# Sheet1.net
KiCad netlist of a schematic drawn in Altium Designer
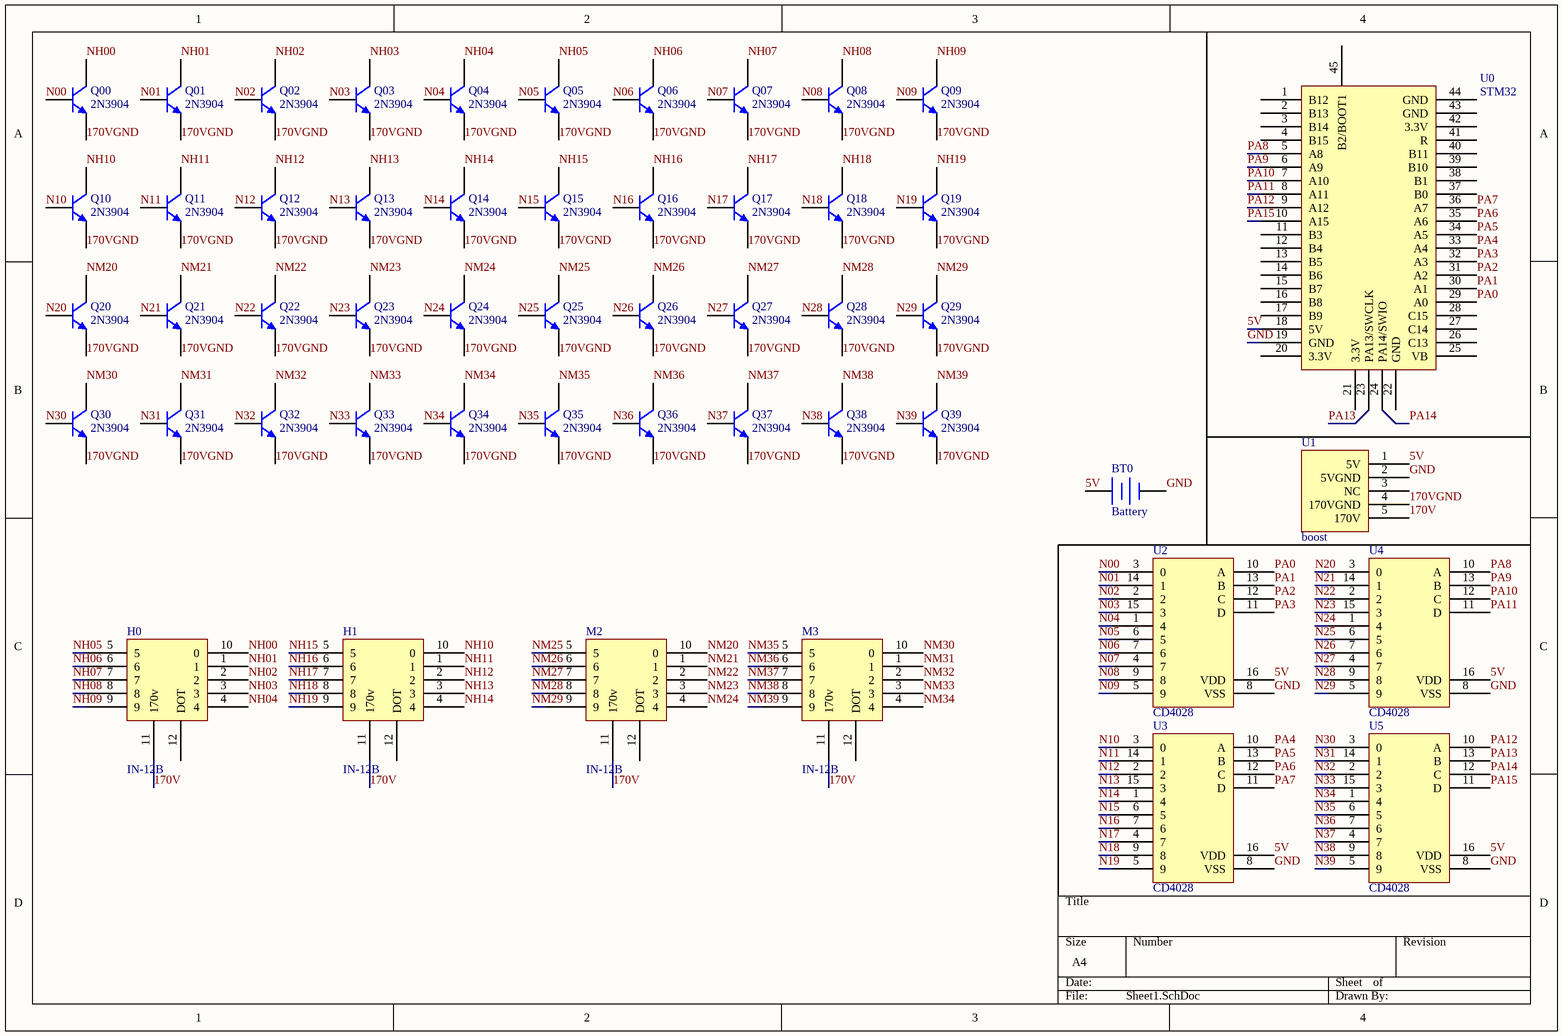
[diagram p0: Sheet1.SchDoc]

(export (version "E")
  (design (tool "Eeschema 10.0.6"))
  (components
    (comp (ref "BT0")
      (value "Battery")
      (footprint "BAT-2")
      (description "Multicell Battery")
      (fields (field (name "PUBLISHER") "Altium Limited"))
      (libsource (lib "Miscellaneous Devices") (part "Battery"))
    )
    (comp (ref "H0") (value "IN-12B") (footprint "IN-12B base") (libsource (lib "IN-12B") (part "IN-12B")))
    (comp (ref "H1") (value "IN-12B") (footprint "IN-12B base") (libsource (lib "IN-12B") (part "IN-12B")))
    (comp (ref "M2") (value "IN-12B") (footprint "IN-12B base") (libsource (lib "IN-12B") (part "IN-12B")))
    (comp (ref "M3") (value "IN-12B") (footprint "IN-12B base") (libsource (lib "IN-12B") (part "IN-12B")))
    (comp (ref "Q00")
      (value "2N3904")
      (footprint "PcbLib1:TO-92")
      (description "NPN General Purpose Amplifier")
      (fields (field (name "PUBLISHER") "Altium Limited"))
      (libsource (lib "Miscellaneous Devices") (part "2N3904"))
    )
    (comp (ref "Q01")
      (value "2N3904")
      (footprint "TO-92")
      (description "NPN General Purpose Amplifier")
      (fields (field (name "PUBLISHER") "Altium Limited"))
      (libsource (lib "Miscellaneous Devices") (part "2N3904"))
    )
    (comp (ref "Q02")
      (value "2N3904")
      (footprint "TO-92")
      (description "NPN General Purpose Amplifier")
      (fields (field (name "PUBLISHER") "Altium Limited"))
      (libsource (lib "Miscellaneous Devices") (part "2N3904"))
    )
    (comp (ref "Q03")
      (value "2N3904")
      (footprint "TO-92")
      (description "NPN General Purpose Amplifier")
      (fields (field (name "PUBLISHER") "Altium Limited"))
      (libsource (lib "Miscellaneous Devices") (part "2N3904"))
    )
    (comp (ref "Q04")
      (value "2N3904")
      (footprint "TO-92")
      (description "NPN General Purpose Amplifier")
      (fields (field (name "PUBLISHER") "Altium Limited"))
      (libsource (lib "Miscellaneous Devices") (part "2N3904"))
    )
    (comp (ref "Q05")
      (value "2N3904")
      (footprint "TO-92")
      (description "NPN General Purpose Amplifier")
      (fields (field (name "PUBLISHER") "Altium Limited"))
      (libsource (lib "Miscellaneous Devices") (part "2N3904"))
    )
    (comp (ref "Q06")
      (value "2N3904")
      (footprint "TO-92")
      (description "NPN General Purpose Amplifier")
      (fields (field (name "PUBLISHER") "Altium Limited"))
      (libsource (lib "Miscellaneous Devices") (part "2N3904"))
    )
    (comp (ref "Q07")
      (value "2N3904")
      (footprint "TO-92")
      (description "NPN General Purpose Amplifier")
      (fields (field (name "PUBLISHER") "Altium Limited"))
      (libsource (lib "Miscellaneous Devices") (part "2N3904"))
    )
    (comp (ref "Q08")
      (value "2N3904")
      (footprint "TO-92")
      (description "NPN General Purpose Amplifier")
      (fields (field (name "PUBLISHER") "Altium Limited"))
      (libsource (lib "Miscellaneous Devices") (part "2N3904"))
    )
    (comp (ref "Q09")
      (value "2N3904")
      (footprint "TO-92")
      (description "NPN General Purpose Amplifier")
      (fields (field (name "PUBLISHER") "Altium Limited"))
      (libsource (lib "Miscellaneous Devices") (part "2N3904"))
    )
    (comp (ref "Q10")
      (value "2N3904")
      (footprint "TO-92")
      (description "NPN General Purpose Amplifier")
      (fields (field (name "PUBLISHER") "Altium Limited"))
      (libsource (lib "Miscellaneous Devices") (part "2N3904"))
    )
    (comp (ref "Q11")
      (value "2N3904")
      (footprint "TO-92")
      (description "NPN General Purpose Amplifier")
      (fields (field (name "PUBLISHER") "Altium Limited"))
      (libsource (lib "Miscellaneous Devices") (part "2N3904"))
    )
    (comp (ref "Q12")
      (value "2N3904")
      (footprint "TO-92")
      (description "NPN General Purpose Amplifier")
      (fields (field (name "PUBLISHER") "Altium Limited"))
      (libsource (lib "Miscellaneous Devices") (part "2N3904"))
    )
    (comp (ref "Q13")
      (value "2N3904")
      (footprint "TO-92")
      (description "NPN General Purpose Amplifier")
      (fields (field (name "PUBLISHER") "Altium Limited"))
      (libsource (lib "Miscellaneous Devices") (part "2N3904"))
    )
    (comp (ref "Q14")
      (value "2N3904")
      (footprint "TO-92")
      (description "NPN General Purpose Amplifier")
      (fields (field (name "PUBLISHER") "Altium Limited"))
      (libsource (lib "Miscellaneous Devices") (part "2N3904"))
    )
    (comp (ref "Q15")
      (value "2N3904")
      (footprint "TO-92")
      (description "NPN General Purpose Amplifier")
      (fields (field (name "PUBLISHER") "Altium Limited"))
      (libsource (lib "Miscellaneous Devices") (part "2N3904"))
    )
    (comp (ref "Q16")
      (value "2N3904")
      (footprint "TO-92")
      (description "NPN General Purpose Amplifier")
      (fields (field (name "PUBLISHER") "Altium Limited"))
      (libsource (lib "Miscellaneous Devices") (part "2N3904"))
    )
    (comp (ref "Q17")
      (value "2N3904")
      (footprint "TO-92")
      (description "NPN General Purpose Amplifier")
      (fields (field (name "PUBLISHER") "Altium Limited"))
      (libsource (lib "Miscellaneous Devices") (part "2N3904"))
    )
    (comp (ref "Q18")
      (value "2N3904")
      (footprint "TO-92")
      (description "NPN General Purpose Amplifier")
      (fields (field (name "PUBLISHER") "Altium Limited"))
      (libsource (lib "Miscellaneous Devices") (part "2N3904"))
    )
    (comp (ref "Q19")
      (value "2N3904")
      (footprint "TO-92")
      (description "NPN General Purpose Amplifier")
      (fields (field (name "PUBLISHER") "Altium Limited"))
      (libsource (lib "Miscellaneous Devices") (part "2N3904"))
    )
    (comp (ref "Q20")
      (value "2N3904")
      (footprint "TO-92")
      (description "NPN General Purpose Amplifier")
      (fields (field (name "PUBLISHER") "Altium Limited"))
      (libsource (lib "Miscellaneous Devices") (part "2N3904"))
    )
    (comp (ref "Q21")
      (value "2N3904")
      (footprint "TO-92")
      (description "NPN General Purpose Amplifier")
      (fields (field (name "PUBLISHER") "Altium Limited"))
      (libsource (lib "Miscellaneous Devices") (part "2N3904"))
    )
    (comp (ref "Q22")
      (value "2N3904")
      (footprint "TO-92")
      (description "NPN General Purpose Amplifier")
      (fields (field (name "PUBLISHER") "Altium Limited"))
      (libsource (lib "Miscellaneous Devices") (part "2N3904"))
    )
    (comp (ref "Q23")
      (value "2N3904")
      (footprint "TO-92")
      (description "NPN General Purpose Amplifier")
      (fields (field (name "PUBLISHER") "Altium Limited"))
      (libsource (lib "Miscellaneous Devices") (part "2N3904"))
    )
    (comp (ref "Q24")
      (value "2N3904")
      (footprint "TO-92")
      (description "NPN General Purpose Amplifier")
      (fields (field (name "PUBLISHER") "Altium Limited"))
      (libsource (lib "Miscellaneous Devices") (part "2N3904"))
    )
    (comp (ref "Q25")
      (value "2N3904")
      (footprint "TO-92")
      (description "NPN General Purpose Amplifier")
      (fields (field (name "PUBLISHER") "Altium Limited"))
      (libsource (lib "Miscellaneous Devices") (part "2N3904"))
    )
    (comp (ref "Q26")
      (value "2N3904")
      (footprint "TO-92")
      (description "NPN General Purpose Amplifier")
      (fields (field (name "PUBLISHER") "Altium Limited"))
      (libsource (lib "Miscellaneous Devices") (part "2N3904"))
    )
    (comp (ref "Q27")
      (value "2N3904")
      (footprint "TO-92")
      (description "NPN General Purpose Amplifier")
      (fields (field (name "PUBLISHER") "Altium Limited"))
      (libsource (lib "Miscellaneous Devices") (part "2N3904"))
    )
    (comp (ref "Q28")
      (value "2N3904")
      (footprint "TO-92")
      (description "NPN General Purpose Amplifier")
      (fields (field (name "PUBLISHER") "Altium Limited"))
      (libsource (lib "Miscellaneous Devices") (part "2N3904"))
    )
    (comp (ref "Q29")
      (value "2N3904")
      (footprint "TO-92")
      (description "NPN General Purpose Amplifier")
      (fields (field (name "PUBLISHER") "Altium Limited"))
      (libsource (lib "Miscellaneous Devices") (part "2N3904"))
    )
    (comp (ref "Q30")
      (value "2N3904")
      (footprint "TO-92")
      (description "NPN General Purpose Amplifier")
      (fields (field (name "PUBLISHER") "Altium Limited"))
      (libsource (lib "Miscellaneous Devices") (part "2N3904"))
    )
    (comp (ref "Q31")
      (value "2N3904")
      (footprint "TO-92")
      (description "NPN General Purpose Amplifier")
      (fields (field (name "PUBLISHER") "Altium Limited"))
      (libsource (lib "Miscellaneous Devices") (part "2N3904"))
    )
    (comp (ref "Q32")
      (value "2N3904")
      (footprint "TO-92")
      (description "NPN General Purpose Amplifier")
      (fields (field (name "PUBLISHER") "Altium Limited"))
      (libsource (lib "Miscellaneous Devices") (part "2N3904"))
    )
    (comp (ref "Q33")
      (value "2N3904")
      (footprint "TO-92")
      (description "NPN General Purpose Amplifier")
      (fields (field (name "PUBLISHER") "Altium Limited"))
      (libsource (lib "Miscellaneous Devices") (part "2N3904"))
    )
    (comp (ref "Q34")
      (value "2N3904")
      (footprint "TO-92")
      (description "NPN General Purpose Amplifier")
      (fields (field (name "PUBLISHER") "Altium Limited"))
      (libsource (lib "Miscellaneous Devices") (part "2N3904"))
    )
    (comp (ref "Q35")
      (value "2N3904")
      (footprint "TO-92")
      (description "NPN General Purpose Amplifier")
      (fields (field (name "PUBLISHER") "Altium Limited"))
      (libsource (lib "Miscellaneous Devices") (part "2N3904"))
    )
    (comp (ref "Q36")
      (value "2N3904")
      (footprint "TO-92")
      (description "NPN General Purpose Amplifier")
      (fields (field (name "PUBLISHER") "Altium Limited"))
      (libsource (lib "Miscellaneous Devices") (part "2N3904"))
    )
    (comp (ref "Q37")
      (value "2N3904")
      (footprint "TO-92")
      (description "NPN General Purpose Amplifier")
      (fields (field (name "PUBLISHER") "Altium Limited"))
      (libsource (lib "Miscellaneous Devices") (part "2N3904"))
    )
    (comp (ref "Q38")
      (value "2N3904")
      (footprint "TO-92")
      (description "NPN General Purpose Amplifier")
      (fields (field (name "PUBLISHER") "Altium Limited"))
      (libsource (lib "Miscellaneous Devices") (part "2N3904"))
    )
    (comp (ref "Q39")
      (value "2N3904")
      (footprint "TO-92")
      (description "NPN General Purpose Amplifier")
      (fields (field (name "PUBLISHER") "Altium Limited"))
      (libsource (lib "Miscellaneous Devices") (part "2N3904"))
    )
    (comp (ref "U0") (value "STM32") (footprint "STM32") (libsource (lib "stm32") (part "STM32")))
    (comp (ref "U1") (value "boost") (footprint "HDR1X5") (libsource (lib "boost") (part "boost")))
    (comp (ref "U2") (value "CD4028") (footprint "CD4028") (libsource (lib "CD4028") (part "CD4028")))
    (comp (ref "U3") (value "CD4028") (footprint "CD4028") (libsource (lib "CD4028") (part "CD4028")))
    (comp (ref "U4") (value "CD4028") (footprint "CD4028") (libsource (lib "CD4028") (part "CD4028")))
    (comp (ref "U5") (value "CD4028") (footprint "CD4028") (libsource (lib "CD4028") (part "CD4028")))
  )
  (nets
    (net (code "1") (name "/5V") (class "Default")
      (node (ref "BT0") (pin "1") (pinfunction "+_1") (pintype "passive"))
      (node (ref "U0") (pin "18") (pinfunction "5V_18") (pintype "passive"))
      (node (ref "U1") (pin "1") (pinfunction "5V_1") (pintype "passive"))
      (node (ref "U2") (pin "16") (pinfunction "VDD_16") (pintype "passive"))
      (node (ref "U3") (pin "16") (pinfunction "VDD_16") (pintype "passive"))
      (node (ref "U4") (pin "16") (pinfunction "VDD_16") (pintype "passive"))
      (node (ref "U5") (pin "16") (pinfunction "VDD_16") (pintype "passive"))
    )
    (net (code "2") (name "/170V") (class "Default")
      (node (ref "H0") (pin "11") (pinfunction "170v_11") (pintype "passive"))
      (node (ref "H1") (pin "11") (pinfunction "170v_11") (pintype "passive"))
      (node (ref "M2") (pin "11") (pinfunction "170v_11") (pintype "passive"))
      (node (ref "M3") (pin "11") (pinfunction "170v_11") (pintype "passive"))
      (node (ref "U1") (pin "5") (pinfunction "170V_5") (pintype "passive"))
    )
    (net (code "3") (name "/170VGND") (class "Default")
      (node (ref "Q00") (pin "1") (pinfunction "E_1") (pintype "passive"))
      (node (ref "Q01") (pin "1") (pinfunction "E_1") (pintype "passive"))
      (node (ref "Q02") (pin "1") (pinfunction "E_1") (pintype "passive"))
      (node (ref "Q03") (pin "1") (pinfunction "E_1") (pintype "passive"))
      (node (ref "Q04") (pin "1") (pinfunction "E_1") (pintype "passive"))
      (node (ref "Q05") (pin "1") (pinfunction "E_1") (pintype "passive"))
      (node (ref "Q06") (pin "1") (pinfunction "E_1") (pintype "passive"))
      (node (ref "Q07") (pin "1") (pinfunction "E_1") (pintype "passive"))
      (node (ref "Q08") (pin "1") (pinfunction "E_1") (pintype "passive"))
      (node (ref "Q09") (pin "1") (pinfunction "E_1") (pintype "passive"))
      (node (ref "Q10") (pin "1") (pinfunction "E_1") (pintype "passive"))
      (node (ref "Q11") (pin "1") (pinfunction "E_1") (pintype "passive"))
      (node (ref "Q12") (pin "1") (pinfunction "E_1") (pintype "passive"))
      (node (ref "Q13") (pin "1") (pinfunction "E_1") (pintype "passive"))
      (node (ref "Q14") (pin "1") (pinfunction "E_1") (pintype "passive"))
      (node (ref "Q15") (pin "1") (pinfunction "E_1") (pintype "passive"))
      (node (ref "Q16") (pin "1") (pinfunction "E_1") (pintype "passive"))
      (node (ref "Q17") (pin "1") (pinfunction "E_1") (pintype "passive"))
      (node (ref "Q18") (pin "1") (pinfunction "E_1") (pintype "passive"))
      (node (ref "Q19") (pin "1") (pinfunction "E_1") (pintype "passive"))
      (node (ref "Q20") (pin "1") (pinfunction "E_1") (pintype "passive"))
      (node (ref "Q21") (pin "1") (pinfunction "E_1") (pintype "passive"))
      (node (ref "Q22") (pin "1") (pinfunction "E_1") (pintype "passive"))
      (node (ref "Q23") (pin "1") (pinfunction "E_1") (pintype "passive"))
      (node (ref "Q24") (pin "1") (pinfunction "E_1") (pintype "passive"))
      (node (ref "Q25") (pin "1") (pinfunction "E_1") (pintype "passive"))
      (node (ref "Q26") (pin "1") (pinfunction "E_1") (pintype "passive"))
      (node (ref "Q27") (pin "1") (pinfunction "E_1") (pintype "passive"))
      (node (ref "Q28") (pin "1") (pinfunction "E_1") (pintype "passive"))
      (node (ref "Q29") (pin "1") (pinfunction "E_1") (pintype "passive"))
      (node (ref "Q30") (pin "1") (pinfunction "E_1") (pintype "passive"))
      (node (ref "Q31") (pin "1") (pinfunction "E_1") (pintype "passive"))
      (node (ref "Q32") (pin "1") (pinfunction "E_1") (pintype "passive"))
      (node (ref "Q33") (pin "1") (pinfunction "E_1") (pintype "passive"))
      (node (ref "Q34") (pin "1") (pinfunction "E_1") (pintype "passive"))
      (node (ref "Q35") (pin "1") (pinfunction "E_1") (pintype "passive"))
      (node (ref "Q36") (pin "1") (pinfunction "E_1") (pintype "passive"))
      (node (ref "Q37") (pin "1") (pinfunction "E_1") (pintype "passive"))
      (node (ref "Q38") (pin "1") (pinfunction "E_1") (pintype "passive"))
      (node (ref "Q39") (pin "1") (pinfunction "E_1") (pintype "passive"))
      (node (ref "U1") (pin "4") (pinfunction "170VGND_4") (pintype "passive"))
    )
    (net (code "4") (name "/GND") (class "Default")
      (node (ref "BT0") (pin "2") (pinfunction "-_2") (pintype "passive"))
      (node (ref "U0") (pin "19") (pinfunction "GND_19") (pintype "passive"))
      (node (ref "U1") (pin "2") (pinfunction "5VGND_2") (pintype "passive"))
      (node (ref "U2") (pin "8") (pinfunction "VSS_8") (pintype "passive"))
      (node (ref "U3") (pin "8") (pinfunction "VSS_8") (pintype "passive"))
      (node (ref "U4") (pin "8") (pinfunction "VSS_8") (pintype "passive"))
      (node (ref "U5") (pin "8") (pinfunction "VSS_8") (pintype "passive"))
    )
    (net (code "5") (name "/N00") (class "Default")
      (node (ref "Q00") (pin "2") (pinfunction "B_2") (pintype "passive"))
      (node (ref "U2") (pin "3") (pinfunction "0_3") (pintype "passive"))
    )
    (net (code "6") (name "/N01") (class "Default")
      (node (ref "Q01") (pin "2") (pinfunction "B_2") (pintype "passive"))
      (node (ref "U2") (pin "14") (pinfunction "1_14") (pintype "passive"))
    )
    (net (code "7") (name "/N02") (class "Default")
      (node (ref "Q02") (pin "2") (pinfunction "B_2") (pintype "passive"))
      (node (ref "U2") (pin "2") (pinfunction "2_2") (pintype "passive"))
    )
    (net (code "8") (name "/N03") (class "Default")
      (node (ref "Q03") (pin "2") (pinfunction "B_2") (pintype "passive"))
      (node (ref "U2") (pin "15") (pinfunction "3_15") (pintype "passive"))
    )
    (net (code "9") (name "/N04") (class "Default")
      (node (ref "Q04") (pin "2") (pinfunction "B_2") (pintype "passive"))
      (node (ref "U2") (pin "1") (pinfunction "4_1") (pintype "passive"))
    )
    (net (code "10") (name "/N05") (class "Default")
      (node (ref "Q05") (pin "2") (pinfunction "B_2") (pintype "passive"))
      (node (ref "U2") (pin "6") (pinfunction "5_6") (pintype "passive"))
    )
    (net (code "11") (name "/N06") (class "Default")
      (node (ref "Q06") (pin "2") (pinfunction "B_2") (pintype "passive"))
      (node (ref "U2") (pin "7") (pinfunction "6_7") (pintype "passive"))
    )
    (net (code "12") (name "/N07") (class "Default")
      (node (ref "Q07") (pin "2") (pinfunction "B_2") (pintype "passive"))
      (node (ref "U2") (pin "4") (pinfunction "7_4") (pintype "passive"))
    )
    (net (code "13") (name "/N08") (class "Default")
      (node (ref "Q08") (pin "2") (pinfunction "B_2") (pintype "passive"))
      (node (ref "U2") (pin "9") (pinfunction "8_9") (pintype "passive"))
    )
    (net (code "14") (name "/N09") (class "Default")
      (node (ref "Q09") (pin "2") (pinfunction "B_2") (pintype "passive"))
      (node (ref "U2") (pin "5") (pinfunction "9_5") (pintype "passive"))
    )
    (net (code "15") (name "/N10") (class "Default")
      (node (ref "Q10") (pin "2") (pinfunction "B_2") (pintype "passive"))
      (node (ref "U3") (pin "3") (pinfunction "0_3") (pintype "passive"))
    )
    (net (code "16") (name "/N11") (class "Default")
      (node (ref "Q11") (pin "2") (pinfunction "B_2") (pintype "passive"))
      (node (ref "U3") (pin "14") (pinfunction "1_14") (pintype "passive"))
    )
    (net (code "17") (name "/N12") (class "Default")
      (node (ref "Q12") (pin "2") (pinfunction "B_2") (pintype "passive"))
      (node (ref "U3") (pin "2") (pinfunction "2_2") (pintype "passive"))
    )
    (net (code "18") (name "/N13") (class "Default")
      (node (ref "Q13") (pin "2") (pinfunction "B_2") (pintype "passive"))
      (node (ref "U3") (pin "15") (pinfunction "3_15") (pintype "passive"))
    )
    (net (code "19") (name "/N14") (class "Default")
      (node (ref "Q14") (pin "2") (pinfunction "B_2") (pintype "passive"))
      (node (ref "U3") (pin "1") (pinfunction "4_1") (pintype "passive"))
    )
    (net (code "20") (name "/N15") (class "Default")
      (node (ref "Q15") (pin "2") (pinfunction "B_2") (pintype "passive"))
      (node (ref "U3") (pin "6") (pinfunction "5_6") (pintype "passive"))
    )
    (net (code "21") (name "/N16") (class "Default")
      (node (ref "Q16") (pin "2") (pinfunction "B_2") (pintype "passive"))
      (node (ref "U3") (pin "7") (pinfunction "6_7") (pintype "passive"))
    )
    (net (code "22") (name "/N17") (class "Default")
      (node (ref "Q17") (pin "2") (pinfunction "B_2") (pintype "passive"))
      (node (ref "U3") (pin "4") (pinfunction "7_4") (pintype "passive"))
    )
    (net (code "23") (name "/N18") (class "Default")
      (node (ref "Q18") (pin "2") (pinfunction "B_2") (pintype "passive"))
      (node (ref "U3") (pin "9") (pinfunction "8_9") (pintype "passive"))
    )
    (net (code "24") (name "/N19") (class "Default")
      (node (ref "Q19") (pin "2") (pinfunction "B_2") (pintype "passive"))
      (node (ref "U3") (pin "5") (pinfunction "9_5") (pintype "passive"))
    )
    (net (code "25") (name "/N20") (class "Default")
      (node (ref "Q20") (pin "2") (pinfunction "B_2") (pintype "passive"))
      (node (ref "U4") (pin "3") (pinfunction "0_3") (pintype "passive"))
    )
    (net (code "26") (name "/N21") (class "Default")
      (node (ref "Q21") (pin "2") (pinfunction "B_2") (pintype "passive"))
      (node (ref "U4") (pin "14") (pinfunction "1_14") (pintype "passive"))
    )
    (net (code "27") (name "/N22") (class "Default")
      (node (ref "Q22") (pin "2") (pinfunction "B_2") (pintype "passive"))
      (node (ref "U4") (pin "2") (pinfunction "2_2") (pintype "passive"))
    )
    (net (code "28") (name "/N23") (class "Default")
      (node (ref "Q23") (pin "2") (pinfunction "B_2") (pintype "passive"))
      (node (ref "U4") (pin "15") (pinfunction "3_15") (pintype "passive"))
    )
    (net (code "29") (name "/N24") (class "Default")
      (node (ref "Q24") (pin "2") (pinfunction "B_2") (pintype "passive"))
      (node (ref "U4") (pin "1") (pinfunction "4_1") (pintype "passive"))
    )
    (net (code "30") (name "/N25") (class "Default")
      (node (ref "Q25") (pin "2") (pinfunction "B_2") (pintype "passive"))
      (node (ref "U4") (pin "6") (pinfunction "5_6") (pintype "passive"))
    )
    (net (code "31") (name "/N26") (class "Default")
      (node (ref "Q26") (pin "2") (pinfunction "B_2") (pintype "passive"))
      (node (ref "U4") (pin "7") (pinfunction "6_7") (pintype "passive"))
    )
    (net (code "32") (name "/N27") (class "Default")
      (node (ref "Q27") (pin "2") (pinfunction "B_2") (pintype "passive"))
      (node (ref "U4") (pin "4") (pinfunction "7_4") (pintype "passive"))
    )
    (net (code "33") (name "/N28") (class "Default")
      (node (ref "Q28") (pin "2") (pinfunction "B_2") (pintype "passive"))
      (node (ref "U4") (pin "9") (pinfunction "8_9") (pintype "passive"))
    )
    (net (code "34") (name "/N29") (class "Default")
      (node (ref "Q29") (pin "2") (pinfunction "B_2") (pintype "passive"))
      (node (ref "U4") (pin "5") (pinfunction "9_5") (pintype "passive"))
    )
    (net (code "35") (name "/N30") (class "Default")
      (node (ref "Q30") (pin "2") (pinfunction "B_2") (pintype "passive"))
      (node (ref "U5") (pin "3") (pinfunction "0_3") (pintype "passive"))
    )
    (net (code "36") (name "/N31") (class "Default")
      (node (ref "Q31") (pin "2") (pinfunction "B_2") (pintype "passive"))
      (node (ref "U5") (pin "14") (pinfunction "1_14") (pintype "passive"))
    )
    (net (code "37") (name "/N32") (class "Default")
      (node (ref "Q32") (pin "2") (pinfunction "B_2") (pintype "passive"))
      (node (ref "U5") (pin "2") (pinfunction "2_2") (pintype "passive"))
    )
    (net (code "38") (name "/N33") (class "Default")
      (node (ref "Q33") (pin "2") (pinfunction "B_2") (pintype "passive"))
      (node (ref "U5") (pin "15") (pinfunction "3_15") (pintype "passive"))
    )
    (net (code "39") (name "/N34") (class "Default")
      (node (ref "Q34") (pin "2") (pinfunction "B_2") (pintype "passive"))
      (node (ref "U5") (pin "1") (pinfunction "4_1") (pintype "passive"))
    )
    (net (code "40") (name "/N35") (class "Default")
      (node (ref "Q35") (pin "2") (pinfunction "B_2") (pintype "passive"))
      (node (ref "U5") (pin "6") (pinfunction "5_6") (pintype "passive"))
    )
    (net (code "41") (name "/N36") (class "Default")
      (node (ref "Q36") (pin "2") (pinfunction "B_2") (pintype "passive"))
      (node (ref "U5") (pin "7") (pinfunction "6_7") (pintype "passive"))
    )
    (net (code "42") (name "/N37") (class "Default")
      (node (ref "Q37") (pin "2") (pinfunction "B_2") (pintype "passive"))
      (node (ref "U5") (pin "4") (pinfunction "7_4") (pintype "passive"))
    )
    (net (code "43") (name "/N38") (class "Default")
      (node (ref "Q38") (pin "2") (pinfunction "B_2") (pintype "passive"))
      (node (ref "U5") (pin "9") (pinfunction "8_9") (pintype "passive"))
    )
    (net (code "44") (name "/N39") (class "Default")
      (node (ref "Q39") (pin "2") (pinfunction "B_2") (pintype "passive"))
      (node (ref "U5") (pin "5") (pinfunction "9_5") (pintype "passive"))
    )
    (net (code "45") (name "/NH00") (class "Default")
      (node (ref "H0") (pin "10") (pinfunction "0_10") (pintype "passive"))
      (node (ref "Q00") (pin "3") (pinfunction "C_3") (pintype "passive"))
    )
    (net (code "46") (name "/NH01") (class "Default")
      (node (ref "H0") (pin "1") (pinfunction "1_1") (pintype "passive"))
      (node (ref "Q01") (pin "3") (pinfunction "C_3") (pintype "passive"))
    )
    (net (code "47") (name "/NH02") (class "Default")
      (node (ref "H0") (pin "2") (pinfunction "2_2") (pintype "passive"))
      (node (ref "Q02") (pin "3") (pinfunction "C_3") (pintype "passive"))
    )
    (net (code "48") (name "/NH03") (class "Default")
      (node (ref "H0") (pin "3") (pinfunction "3_3") (pintype "passive"))
      (node (ref "Q03") (pin "3") (pinfunction "C_3") (pintype "passive"))
    )
    (net (code "49") (name "/NH04") (class "Default")
      (node (ref "H0") (pin "4") (pinfunction "4_4") (pintype "passive"))
      (node (ref "Q04") (pin "3") (pinfunction "C_3") (pintype "passive"))
    )
    (net (code "50") (name "/NH05") (class "Default")
      (node (ref "H0") (pin "5") (pinfunction "5_5") (pintype "passive"))
      (node (ref "Q05") (pin "3") (pinfunction "C_3") (pintype "passive"))
    )
    (net (code "51") (name "/NH06") (class "Default")
      (node (ref "H0") (pin "6") (pinfunction "6_6") (pintype "passive"))
      (node (ref "Q06") (pin "3") (pinfunction "C_3") (pintype "passive"))
    )
    (net (code "52") (name "/NH07") (class "Default")
      (node (ref "H0") (pin "7") (pinfunction "7_7") (pintype "passive"))
      (node (ref "Q07") (pin "3") (pinfunction "C_3") (pintype "passive"))
    )
    (net (code "53") (name "/NH08") (class "Default")
      (node (ref "H0") (pin "8") (pinfunction "8_8") (pintype "passive"))
      (node (ref "Q08") (pin "3") (pinfunction "C_3") (pintype "passive"))
    )
    (net (code "54") (name "/NH09") (class "Default")
      (node (ref "H0") (pin "9") (pinfunction "9_9") (pintype "passive"))
      (node (ref "Q09") (pin "3") (pinfunction "C_3") (pintype "passive"))
    )
    (net (code "55") (name "/NH10") (class "Default")
      (node (ref "H1") (pin "10") (pinfunction "0_10") (pintype "passive"))
      (node (ref "Q10") (pin "3") (pinfunction "C_3") (pintype "passive"))
    )
    (net (code "56") (name "/NH11") (class "Default")
      (node (ref "H1") (pin "1") (pinfunction "1_1") (pintype "passive"))
      (node (ref "Q11") (pin "3") (pinfunction "C_3") (pintype "passive"))
    )
    (net (code "57") (name "/NH12") (class "Default")
      (node (ref "H1") (pin "2") (pinfunction "2_2") (pintype "passive"))
      (node (ref "Q12") (pin "3") (pinfunction "C_3") (pintype "passive"))
    )
    (net (code "58") (name "/NH13") (class "Default")
      (node (ref "H1") (pin "3") (pinfunction "3_3") (pintype "passive"))
      (node (ref "Q13") (pin "3") (pinfunction "C_3") (pintype "passive"))
    )
    (net (code "59") (name "/NH14") (class "Default")
      (node (ref "H1") (pin "4") (pinfunction "4_4") (pintype "passive"))
      (node (ref "Q14") (pin "3") (pinfunction "C_3") (pintype "passive"))
    )
    (net (code "60") (name "/NH15") (class "Default")
      (node (ref "H1") (pin "5") (pinfunction "5_5") (pintype "passive"))
      (node (ref "Q15") (pin "3") (pinfunction "C_3") (pintype "passive"))
    )
    (net (code "61") (name "/NH16") (class "Default")
      (node (ref "H1") (pin "6") (pinfunction "6_6") (pintype "passive"))
      (node (ref "Q16") (pin "3") (pinfunction "C_3") (pintype "passive"))
    )
    (net (code "62") (name "/NH17") (class "Default")
      (node (ref "H1") (pin "7") (pinfunction "7_7") (pintype "passive"))
      (node (ref "Q17") (pin "3") (pinfunction "C_3") (pintype "passive"))
    )
    (net (code "63") (name "/NH18") (class "Default")
      (node (ref "H1") (pin "8") (pinfunction "8_8") (pintype "passive"))
      (node (ref "Q18") (pin "3") (pinfunction "C_3") (pintype "passive"))
    )
    (net (code "64") (name "/NH19") (class "Default")
      (node (ref "H1") (pin "9") (pinfunction "9_9") (pintype "passive"))
      (node (ref "Q19") (pin "3") (pinfunction "C_3") (pintype "passive"))
    )
    (net (code "65") (name "/NM20") (class "Default")
      (node (ref "M2") (pin "10") (pinfunction "0_10") (pintype "passive"))
      (node (ref "Q20") (pin "3") (pinfunction "C_3") (pintype "passive"))
    )
    (net (code "66") (name "/NM21") (class "Default")
      (node (ref "M2") (pin "1") (pinfunction "1_1") (pintype "passive"))
      (node (ref "Q21") (pin "3") (pinfunction "C_3") (pintype "passive"))
    )
    (net (code "67") (name "/NM22") (class "Default")
      (node (ref "M2") (pin "2") (pinfunction "2_2") (pintype "passive"))
      (node (ref "Q22") (pin "3") (pinfunction "C_3") (pintype "passive"))
    )
    (net (code "68") (name "/NM23") (class "Default")
      (node (ref "M2") (pin "3") (pinfunction "3_3") (pintype "passive"))
      (node (ref "Q23") (pin "3") (pinfunction "C_3") (pintype "passive"))
    )
    (net (code "69") (name "/NM24") (class "Default")
      (node (ref "M2") (pin "4") (pinfunction "4_4") (pintype "passive"))
      (node (ref "Q24") (pin "3") (pinfunction "C_3") (pintype "passive"))
    )
    (net (code "70") (name "/NM25") (class "Default")
      (node (ref "M2") (pin "5") (pinfunction "5_5") (pintype "passive"))
      (node (ref "Q25") (pin "3") (pinfunction "C_3") (pintype "passive"))
    )
    (net (code "71") (name "/NM26") (class "Default")
      (node (ref "M2") (pin "6") (pinfunction "6_6") (pintype "passive"))
      (node (ref "Q26") (pin "3") (pinfunction "C_3") (pintype "passive"))
    )
    (net (code "72") (name "/NM27") (class "Default")
      (node (ref "M2") (pin "7") (pinfunction "7_7") (pintype "passive"))
      (node (ref "Q27") (pin "3") (pinfunction "C_3") (pintype "passive"))
    )
    (net (code "73") (name "/NM28") (class "Default")
      (node (ref "M2") (pin "8") (pinfunction "8_8") (pintype "passive"))
      (node (ref "Q28") (pin "3") (pinfunction "C_3") (pintype "passive"))
    )
    (net (code "74") (name "/NM29") (class "Default")
      (node (ref "M2") (pin "9") (pinfunction "9_9") (pintype "passive"))
      (node (ref "Q29") (pin "3") (pinfunction "C_3") (pintype "passive"))
    )
    (net (code "75") (name "/NM30") (class "Default")
      (node (ref "M3") (pin "10") (pinfunction "0_10") (pintype "passive"))
      (node (ref "Q30") (pin "3") (pinfunction "C_3") (pintype "passive"))
    )
    (net (code "76") (name "/NM31") (class "Default")
      (node (ref "M3") (pin "1") (pinfunction "1_1") (pintype "passive"))
      (node (ref "Q31") (pin "3") (pinfunction "C_3") (pintype "passive"))
    )
    (net (code "77") (name "/NM32") (class "Default")
      (node (ref "M3") (pin "2") (pinfunction "2_2") (pintype "passive"))
      (node (ref "Q32") (pin "3") (pinfunction "C_3") (pintype "passive"))
    )
    (net (code "78") (name "/NM33") (class "Default")
      (node (ref "M3") (pin "3") (pinfunction "3_3") (pintype "passive"))
      (node (ref "Q33") (pin "3") (pinfunction "C_3") (pintype "passive"))
    )
    (net (code "79") (name "/NM34") (class "Default")
      (node (ref "M3") (pin "4") (pinfunction "4_4") (pintype "passive"))
      (node (ref "Q34") (pin "3") (pinfunction "C_3") (pintype "passive"))
    )
    (net (code "80") (name "/NM35") (class "Default")
      (node (ref "M3") (pin "5") (pinfunction "5_5") (pintype "passive"))
      (node (ref "Q35") (pin "3") (pinfunction "C_3") (pintype "passive"))
    )
    (net (code "81") (name "/NM36") (class "Default")
      (node (ref "M3") (pin "6") (pinfunction "6_6") (pintype "passive"))
      (node (ref "Q36") (pin "3") (pinfunction "C_3") (pintype "passive"))
    )
    (net (code "82") (name "/NM37") (class "Default")
      (node (ref "M3") (pin "7") (pinfunction "7_7") (pintype "passive"))
      (node (ref "Q37") (pin "3") (pinfunction "C_3") (pintype "passive"))
    )
    (net (code "83") (name "/NM38") (class "Default")
      (node (ref "M3") (pin "8") (pinfunction "8_8") (pintype "passive"))
      (node (ref "Q38") (pin "3") (pinfunction "C_3") (pintype "passive"))
    )
    (net (code "84") (name "/NM39") (class "Default")
      (node (ref "M3") (pin "9") (pinfunction "9_9") (pintype "passive"))
      (node (ref "Q39") (pin "3") (pinfunction "C_3") (pintype "passive"))
    )
    (net (code "85") (name "/PA0") (class "Default")
      (node (ref "U0") (pin "29") (pinfunction "A0_29") (pintype "passive"))
      (node (ref "U2") (pin "10") (pinfunction "A_10") (pintype "passive"))
    )
    (net (code "86") (name "/PA1") (class "Default")
      (node (ref "U0") (pin "30") (pinfunction "A1_30") (pintype "passive"))
      (node (ref "U2") (pin "13") (pinfunction "B_13") (pintype "passive"))
    )
    (net (code "87") (name "/PA2") (class "Default")
      (node (ref "U0") (pin "31") (pinfunction "A2_31") (pintype "passive"))
      (node (ref "U2") (pin "12") (pinfunction "C_12") (pintype "passive"))
    )
    (net (code "88") (name "/PA3") (class "Default")
      (node (ref "U0") (pin "32") (pinfunction "A3_32") (pintype "passive"))
      (node (ref "U2") (pin "11") (pinfunction "D_11") (pintype "passive"))
    )
    (net (code "89") (name "/PA4") (class "Default")
      (node (ref "U0") (pin "33") (pinfunction "A4_33") (pintype "passive"))
      (node (ref "U3") (pin "10") (pinfunction "A_10") (pintype "passive"))
    )
    (net (code "90") (name "/PA5") (class "Default")
      (node (ref "U0") (pin "34") (pinfunction "A5_34") (pintype "passive"))
      (node (ref "U3") (pin "13") (pinfunction "B_13") (pintype "passive"))
    )
    (net (code "91") (name "/PA6") (class "Default")
      (node (ref "U0") (pin "35") (pinfunction "A6_35") (pintype "passive"))
      (node (ref "U3") (pin "12") (pinfunction "C_12") (pintype "passive"))
    )
    (net (code "92") (name "/PA7") (class "Default")
      (node (ref "U0") (pin "36") (pinfunction "A7_36") (pintype "passive"))
      (node (ref "U3") (pin "11") (pinfunction "D_11") (pintype "passive"))
    )
    (net (code "93") (name "/PA8") (class "Default")
      (node (ref "U0") (pin "5") (pinfunction "A8_5") (pintype "passive"))
      (node (ref "U4") (pin "10") (pinfunction "A_10") (pintype "passive"))
    )
    (net (code "94") (name "/PA9") (class "Default")
      (node (ref "U0") (pin "6") (pinfunction "A9_6") (pintype "passive"))
      (node (ref "U4") (pin "13") (pinfunction "B_13") (pintype "passive"))
    )
    (net (code "95") (name "/PA10") (class "Default")
      (node (ref "U0") (pin "7") (pinfunction "A10_7") (pintype "passive"))
      (node (ref "U4") (pin "12") (pinfunction "C_12") (pintype "passive"))
    )
    (net (code "96") (name "/PA11") (class "Default")
      (node (ref "U0") (pin "8") (pinfunction "A11_8") (pintype "passive"))
      (node (ref "U4") (pin "11") (pinfunction "D_11") (pintype "passive"))
    )
    (net (code "97") (name "/PA12") (class "Default")
      (node (ref "U0") (pin "9") (pinfunction "A12_9") (pintype "passive"))
      (node (ref "U5") (pin "10") (pinfunction "A_10") (pintype "passive"))
    )
    (net (code "98") (name "/PA13") (class "Default")
      (node (ref "U0") (pin "23") (pinfunction "PA13/SWCLK_23") (pintype "passive"))
      (node (ref "U5") (pin "13") (pinfunction "B_13") (pintype "passive"))
    )
    (net (code "99") (name "/PA14") (class "Default")
      (node (ref "U0") (pin "24") (pinfunction "PA14/SWIO_24") (pintype "passive"))
      (node (ref "U5") (pin "12") (pinfunction "C_12") (pintype "passive"))
    )
    (net (code "100") (name "/PA15") (class "Default")
      (node (ref "U0") (pin "10") (pinfunction "A15_10") (pintype "passive"))
      (node (ref "U5") (pin "11") (pinfunction "D_11") (pintype "passive"))
    )
    (net (code "101") (name "unconnected-(H0-DOT-Pad12)") (class "Default")
      (node (ref "H0") (pin "12") (pinfunction "DOT_12") (pintype "passive"))
    )
    (net (code "102") (name "unconnected-(H1-DOT-Pad12)") (class "Default")
      (node (ref "H1") (pin "12") (pinfunction "DOT_12") (pintype "passive"))
    )
    (net (code "103") (name "unconnected-(M2-DOT-Pad12)") (class "Default")
      (node (ref "M2") (pin "12") (pinfunction "DOT_12") (pintype "passive"))
    )
    (net (code "104") (name "unconnected-(M3-DOT-Pad12)") (class "Default")
      (node (ref "M3") (pin "12") (pinfunction "DOT_12") (pintype "passive"))
    )
    (net (code "105") (name "unconnected-(U0-3.3V-Pad20)") (class "Default")
      (node (ref "U0") (pin "20") (pinfunction "3.3V_20") (pintype "passive"))
    )
    (net (code "106") (name "unconnected-(U0-3.3V-Pad21)") (class "Default")
      (node (ref "U0") (pin "21") (pinfunction "3.3V_21") (pintype "passive"))
    )
    (net (code "107") (name "unconnected-(U0-3.3V-Pad42)") (class "Default")
      (node (ref "U0") (pin "42") (pinfunction "3.3V_42") (pintype "passive"))
    )
    (net (code "108") (name "unconnected-(U0-B0-Pad37)") (class "Default")
      (node (ref "U0") (pin "37") (pinfunction "B0_37") (pintype "passive"))
    )
    (net (code "109") (name "unconnected-(U0-B1-Pad38)") (class "Default")
      (node (ref "U0") (pin "38") (pinfunction "B1_38") (pintype "passive"))
    )
    (net (code "110") (name "unconnected-(U0-B2{slash}BOOT1-Pad45)") (class "Default")
      (node (ref "U0") (pin "45") (pinfunction "B2/BOOT1_45") (pintype "passive"))
    )
    (net (code "111") (name "unconnected-(U0-B3-Pad11)") (class "Default")
      (node (ref "U0") (pin "11") (pinfunction "B3_11") (pintype "passive"))
    )
    (net (code "112") (name "unconnected-(U0-B4-Pad12)") (class "Default")
      (node (ref "U0") (pin "12") (pinfunction "B4_12") (pintype "passive"))
    )
    (net (code "113") (name "unconnected-(U0-B5-Pad13)") (class "Default")
      (node (ref "U0") (pin "13") (pinfunction "B5_13") (pintype "passive"))
    )
    (net (code "114") (name "unconnected-(U0-B6-Pad14)") (class "Default")
      (node (ref "U0") (pin "14") (pinfunction "B6_14") (pintype "passive"))
    )
    (net (code "115") (name "unconnected-(U0-B7-Pad15)") (class "Default")
      (node (ref "U0") (pin "15") (pinfunction "B7_15") (pintype "passive"))
    )
    (net (code "116") (name "unconnected-(U0-B8-Pad16)") (class "Default")
      (node (ref "U0") (pin "16") (pinfunction "B8_16") (pintype "passive"))
    )
    (net (code "117") (name "unconnected-(U0-B9-Pad17)") (class "Default")
      (node (ref "U0") (pin "17") (pinfunction "B9_17") (pintype "passive"))
    )
    (net (code "118") (name "unconnected-(U0-B10-Pad39)") (class "Default")
      (node (ref "U0") (pin "39") (pinfunction "B10_39") (pintype "passive"))
    )
    (net (code "119") (name "unconnected-(U0-B11-Pad40)") (class "Default")
      (node (ref "U0") (pin "40") (pinfunction "B11_40") (pintype "passive"))
    )
    (net (code "120") (name "unconnected-(U0-B12-Pad1)") (class "Default")
      (node (ref "U0") (pin "1") (pinfunction "B12_1") (pintype "passive"))
    )
    (net (code "121") (name "unconnected-(U0-B13-Pad2)") (class "Default")
      (node (ref "U0") (pin "2") (pinfunction "B13_2") (pintype "passive"))
    )
    (net (code "122") (name "unconnected-(U0-B14-Pad3)") (class "Default")
      (node (ref "U0") (pin "3") (pinfunction "B14_3") (pintype "passive"))
    )
    (net (code "123") (name "unconnected-(U0-B15-Pad4)") (class "Default")
      (node (ref "U0") (pin "4") (pinfunction "B15_4") (pintype "passive"))
    )
    (net (code "124") (name "unconnected-(U0-C13-Pad26)") (class "Default")
      (node (ref "U0") (pin "26") (pinfunction "C13_26") (pintype "passive"))
    )
    (net (code "125") (name "unconnected-(U0-C14-Pad27)") (class "Default")
      (node (ref "U0") (pin "27") (pinfunction "C14_27") (pintype "passive"))
    )
    (net (code "126") (name "unconnected-(U0-C15-Pad28)") (class "Default")
      (node (ref "U0") (pin "28") (pinfunction "C15_28") (pintype "passive"))
    )
    (net (code "127") (name "unconnected-(U0-GND-Pad22)") (class "Default")
      (node (ref "U0") (pin "22") (pinfunction "GND_22") (pintype "passive"))
    )
    (net (code "128") (name "unconnected-(U0-GND-Pad43)") (class "Default")
      (node (ref "U0") (pin "43") (pinfunction "GND_43") (pintype "passive"))
    )
    (net (code "129") (name "unconnected-(U0-GND-Pad44)") (class "Default")
      (node (ref "U0") (pin "44") (pinfunction "GND_44") (pintype "passive"))
    )
    (net (code "130") (name "unconnected-(U0-R-Pad41)") (class "Default")
      (node (ref "U0") (pin "41") (pinfunction "R_41") (pintype "passive"))
    )
    (net (code "131") (name "unconnected-(U0-VB-Pad25)") (class "Default")
      (node (ref "U0") (pin "25") (pinfunction "VB_25") (pintype "passive"))
    )
    (net (code "132") (name "unconnected-(U1-NC-Pad3)") (class "Default")
      (node (ref "U1") (pin "3") (pinfunction "NC_3") (pintype "passive"))
    )
  )
)
